# SCH_Eric_s-Circuit_2025-10-19_1.net
KiCad netlist of a schematic drawn in EasyEDA
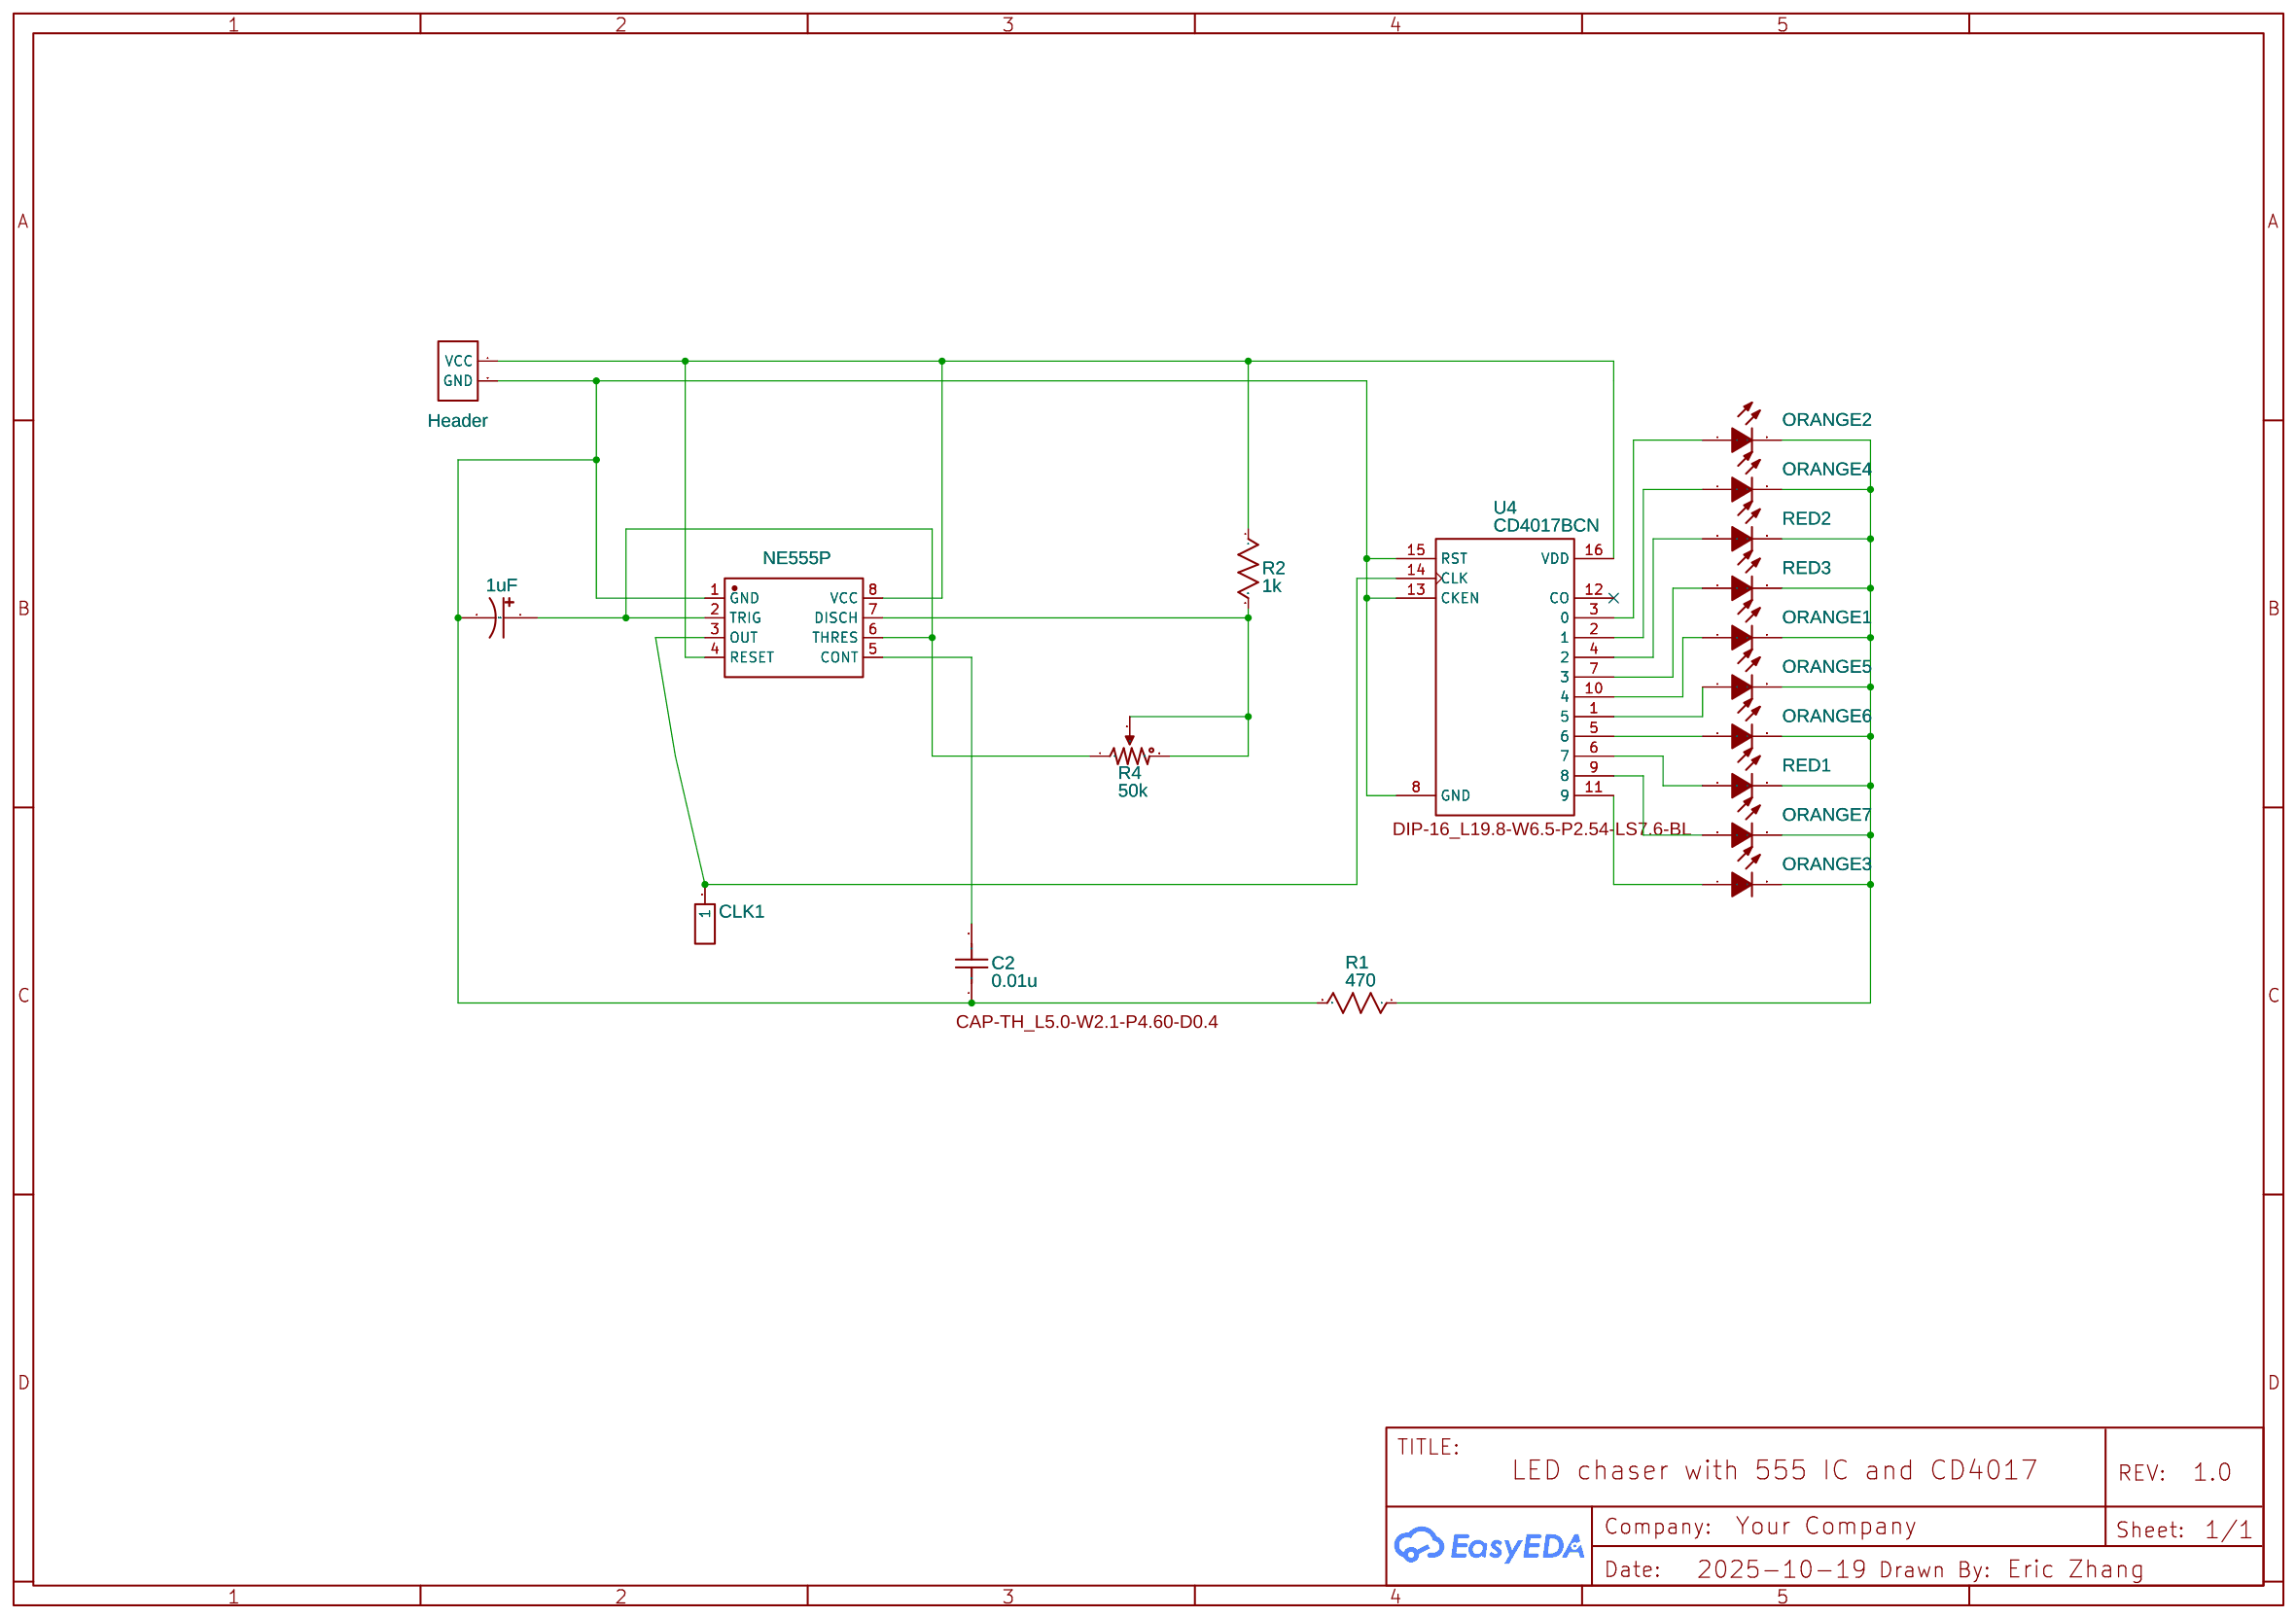
[diagram p0: schematic sheet]

(export (version "E")
  (design (tool "Eeschema 10.0.6"))
  (components
    (comp (ref "C1")
      (value "1uF")
      (fields (field (name "Manufacturer Part") "UVZ1H010MDD") (field (name "Manufacturer") "Nichicon(尼吉康)"))
      (libsource (lib "") (part "UVZ1H010MDD"))
    )
    (comp (ref "C2") (value "0.01u") (libsource (lib "") (part "C_0603_US")))
    (comp (ref "CLK1")
      (value "C81276")
      (fields
        (field (name "Manufacturer Part") "2.54-1*1P针")
        (field (name "Manufacturer") "BOOMELE(Boom Precision Elec)")
      )
      (libsource (lib "") (part "Header-Male-2.54_1x1"))
    )
    (comp (ref "H1") (value "Header") (libsource (lib "") (part "HEADER-FEMALE-2.54_1X2")))
    (comp (ref "ORANGE1") (value "LED_5MM") (libsource (lib "") (part "LED_5MM")))
    (comp (ref "ORANGE2") (value "LED_5MM") (libsource (lib "") (part "LED_5MM")))
    (comp (ref "ORANGE3") (value "LED_5MM") (libsource (lib "") (part "LED_5MM")))
    (comp (ref "ORANGE4") (value "LED_5MM") (libsource (lib "") (part "LED_5MM")))
    (comp (ref "ORANGE5") (value "LED_5MM") (libsource (lib "") (part "LED_5MM")))
    (comp (ref "ORANGE6") (value "LED_5MM") (libsource (lib "") (part "LED_5MM")))
    (comp (ref "ORANGE7") (value "LED_5MM") (libsource (lib "") (part "LED_5MM")))
    (comp (ref "R1")
      (value "470")
      (fields (field (name "Manufacturer Part") "?"))
      (libsource (lib "") (part "Resistor_1"))
    )
    (comp (ref "R2")
      (value "1k")
      (fields (field (name "Manufacturer Part") "?"))
      (libsource (lib "") (part "Resistor"))
    )
    (comp (ref "R4")
      (value "50k")
      (fields (field (name "Manufacturer Part") "?"))
      (libsource (lib "") (part "Potentiometer"))
    )
    (comp (ref "RED1") (value "LED_5MM") (libsource (lib "") (part "LED_5MM_1")))
    (comp (ref "RED2") (value "LED_5MM") (libsource (lib "") (part "LED_5MM_1")))
    (comp (ref "RED3") (value "LED_5MM") (libsource (lib "") (part "LED_5MM_1")))
    (comp (ref "U2")
      (value "NE555P")
      (fields (field (name "Manufacturer") "TI(德州仪器)"))
      (libsource (lib "") (part "NE555P"))
    )
    (comp (ref "U4") (value "CD4017BCN") (libsource (lib "") (part "CD4017BCN")))
  )
  (nets
    (net (code "1") (name "Net-(H1-GND)") (class "Default")
      (node (ref "C1") (pin "2") (pinfunction "2_2") (pintype "unspecified"))
      (node (ref "C2") (pin "1") (pinfunction "1_1") (pintype "unspecified"))
      (node (ref "H1") (pin "2") (pinfunction "GND_2") (pintype "unspecified"))
      (node (ref "R1") (pin "2") (pinfunction "2_2") (pintype "unspecified"))
      (node (ref "U2") (pin "1") (pinfunction "GND_1") (pintype "unspecified"))
      (node (ref "U4") (pin "13") (pinfunction "CKEN_13") (pintype "unspecified"))
      (node (ref "U4") (pin "15") (pinfunction "RST_15") (pintype "unspecified"))
      (node (ref "U4") (pin "8") (pinfunction "GND_8") (pintype "passive"))
    )
    (net (code "2") (name "Net-(H1-VCC)") (class "Default")
      (node (ref "H1") (pin "1") (pinfunction "VCC_1") (pintype "unspecified"))
      (node (ref "R2") (pin "1") (pinfunction "1_1") (pintype "unspecified"))
      (node (ref "U2") (pin "4") (pinfunction "RESET_4") (pintype "unspecified"))
      (node (ref "U2") (pin "8") (pinfunction "VCC_8") (pintype "unspecified"))
      (node (ref "U4") (pin "16") (pinfunction "VDD_16") (pintype "passive"))
    )
    (net (code "3") (name "Net-(ORANGE1-A)") (class "Default")
      (node (ref "ORANGE1") (pin "1") (pinfunction "A_1") (pintype "input"))
      (node (ref "U4") (pin "10") (pinfunction "4_10") (pintype "output"))
    )
    (net (code "4") (name "Net-(ORANGE1-K)") (class "Default")
      (node (ref "ORANGE1") (pin "2") (pinfunction "K_2") (pintype "input"))
      (node (ref "ORANGE2") (pin "2") (pinfunction "K_2") (pintype "input"))
      (node (ref "ORANGE3") (pin "2") (pinfunction "K_2") (pintype "input"))
      (node (ref "ORANGE4") (pin "2") (pinfunction "K_2") (pintype "input"))
      (node (ref "ORANGE5") (pin "2") (pinfunction "K_2") (pintype "input"))
      (node (ref "ORANGE6") (pin "2") (pinfunction "K_2") (pintype "input"))
      (node (ref "ORANGE7") (pin "2") (pinfunction "K_2") (pintype "input"))
      (node (ref "R1") (pin "1") (pinfunction "1_1") (pintype "unspecified"))
      (node (ref "RED1") (pin "2") (pinfunction "K_2") (pintype "input"))
      (node (ref "RED2") (pin "2") (pinfunction "K_2") (pintype "input"))
      (node (ref "RED3") (pin "2") (pinfunction "K_2") (pintype "input"))
    )
    (net (code "5") (name "Net-(ORANGE2-A)") (class "Default")
      (node (ref "ORANGE2") (pin "1") (pinfunction "A_1") (pintype "input"))
      (node (ref "U4") (pin "3") (pinfunction "0_3") (pintype "output"))
    )
    (net (code "6") (name "Net-(ORANGE3-A)") (class "Default")
      (node (ref "ORANGE3") (pin "1") (pinfunction "A_1") (pintype "input"))
      (node (ref "U4") (pin "11") (pinfunction "9_11") (pintype "output"))
    )
    (net (code "7") (name "Net-(ORANGE4-A)") (class "Default")
      (node (ref "ORANGE4") (pin "1") (pinfunction "A_1") (pintype "input"))
      (node (ref "U4") (pin "2") (pinfunction "1_2") (pintype "output"))
    )
    (net (code "8") (name "Net-(ORANGE5-A)") (class "Default")
      (node (ref "ORANGE5") (pin "1") (pinfunction "A_1") (pintype "input"))
      (node (ref "U4") (pin "1") (pinfunction "5_1") (pintype "output"))
    )
    (net (code "9") (name "Net-(ORANGE6-A)") (class "Default")
      (node (ref "ORANGE6") (pin "1") (pinfunction "A_1") (pintype "input"))
      (node (ref "U4") (pin "5") (pinfunction "6_5") (pintype "output"))
    )
    (net (code "10") (name "Net-(ORANGE7-A)") (class "Default")
      (node (ref "ORANGE7") (pin "1") (pinfunction "A_1") (pintype "input"))
      (node (ref "U4") (pin "9") (pinfunction "8_9") (pintype "output"))
    )
    (net (code "11") (name "Net-(R4-2)") (class "Default")
      (node (ref "R2") (pin "2") (pinfunction "2_2") (pintype "unspecified"))
      (node (ref "R4") (pin "2") (pinfunction "3_2") (pintype "unspecified"))
      (node (ref "R4") (pin "3") (pinfunction "2_3") (pintype "unspecified"))
      (node (ref "U2") (pin "7") (pinfunction "DISCH_7") (pintype "unspecified"))
    )
    (net (code "12") (name "Net-(RED1-A)") (class "Default")
      (node (ref "RED1") (pin "1") (pinfunction "A_1") (pintype "input"))
      (node (ref "U4") (pin "6") (pinfunction "7_6") (pintype "output"))
    )
    (net (code "13") (name "Net-(RED2-A)") (class "Default")
      (node (ref "RED2") (pin "1") (pinfunction "A_1") (pintype "input"))
      (node (ref "U4") (pin "4") (pinfunction "2_4") (pintype "output"))
    )
    (net (code "14") (name "Net-(RED3-A)") (class "Default")
      (node (ref "RED3") (pin "1") (pinfunction "A_1") (pintype "input"))
      (node (ref "U4") (pin "7") (pinfunction "3_7") (pintype "output"))
    )
    (net (code "15") (name "Net-(U2-CONT)") (class "Default")
      (node (ref "C2") (pin "2") (pinfunction "2_2") (pintype "unspecified"))
      (node (ref "U2") (pin "5") (pinfunction "CONT_5") (pintype "unspecified"))
    )
    (net (code "16") (name "Net-(U2-OUT)") (class "Default")
      (node (ref "CLK1") (pin "1") (pinfunction "1_1") (pintype "unspecified"))
      (node (ref "U2") (pin "3") (pinfunction "OUT_3") (pintype "unspecified"))
      (node (ref "U4") (pin "14") (pinfunction "CLK_14") (pintype "unspecified"))
    )
    (net (code "17") (name "Net-(U2-THRES)") (class "Default")
      (node (ref "C1") (pin "1") (pinfunction "1_1") (pintype "unspecified"))
      (node (ref "R4") (pin "1") (pinfunction "1_1") (pintype "unspecified"))
      (node (ref "U2") (pin "2") (pinfunction "TRIG_2") (pintype "unspecified"))
      (node (ref "U2") (pin "6") (pinfunction "THRES_6") (pintype "unspecified"))
    )
    (net (code "18") (name "unconnected-(U4-CO-Pad12)") (class "Default")
      (node (ref "U4") (pin "12") (pinfunction "CO_12") (pintype "output+no_connect"))
    )
  )
)
